# ESC-1.net
KiCad netlist of a schematic drawn in EAGLE
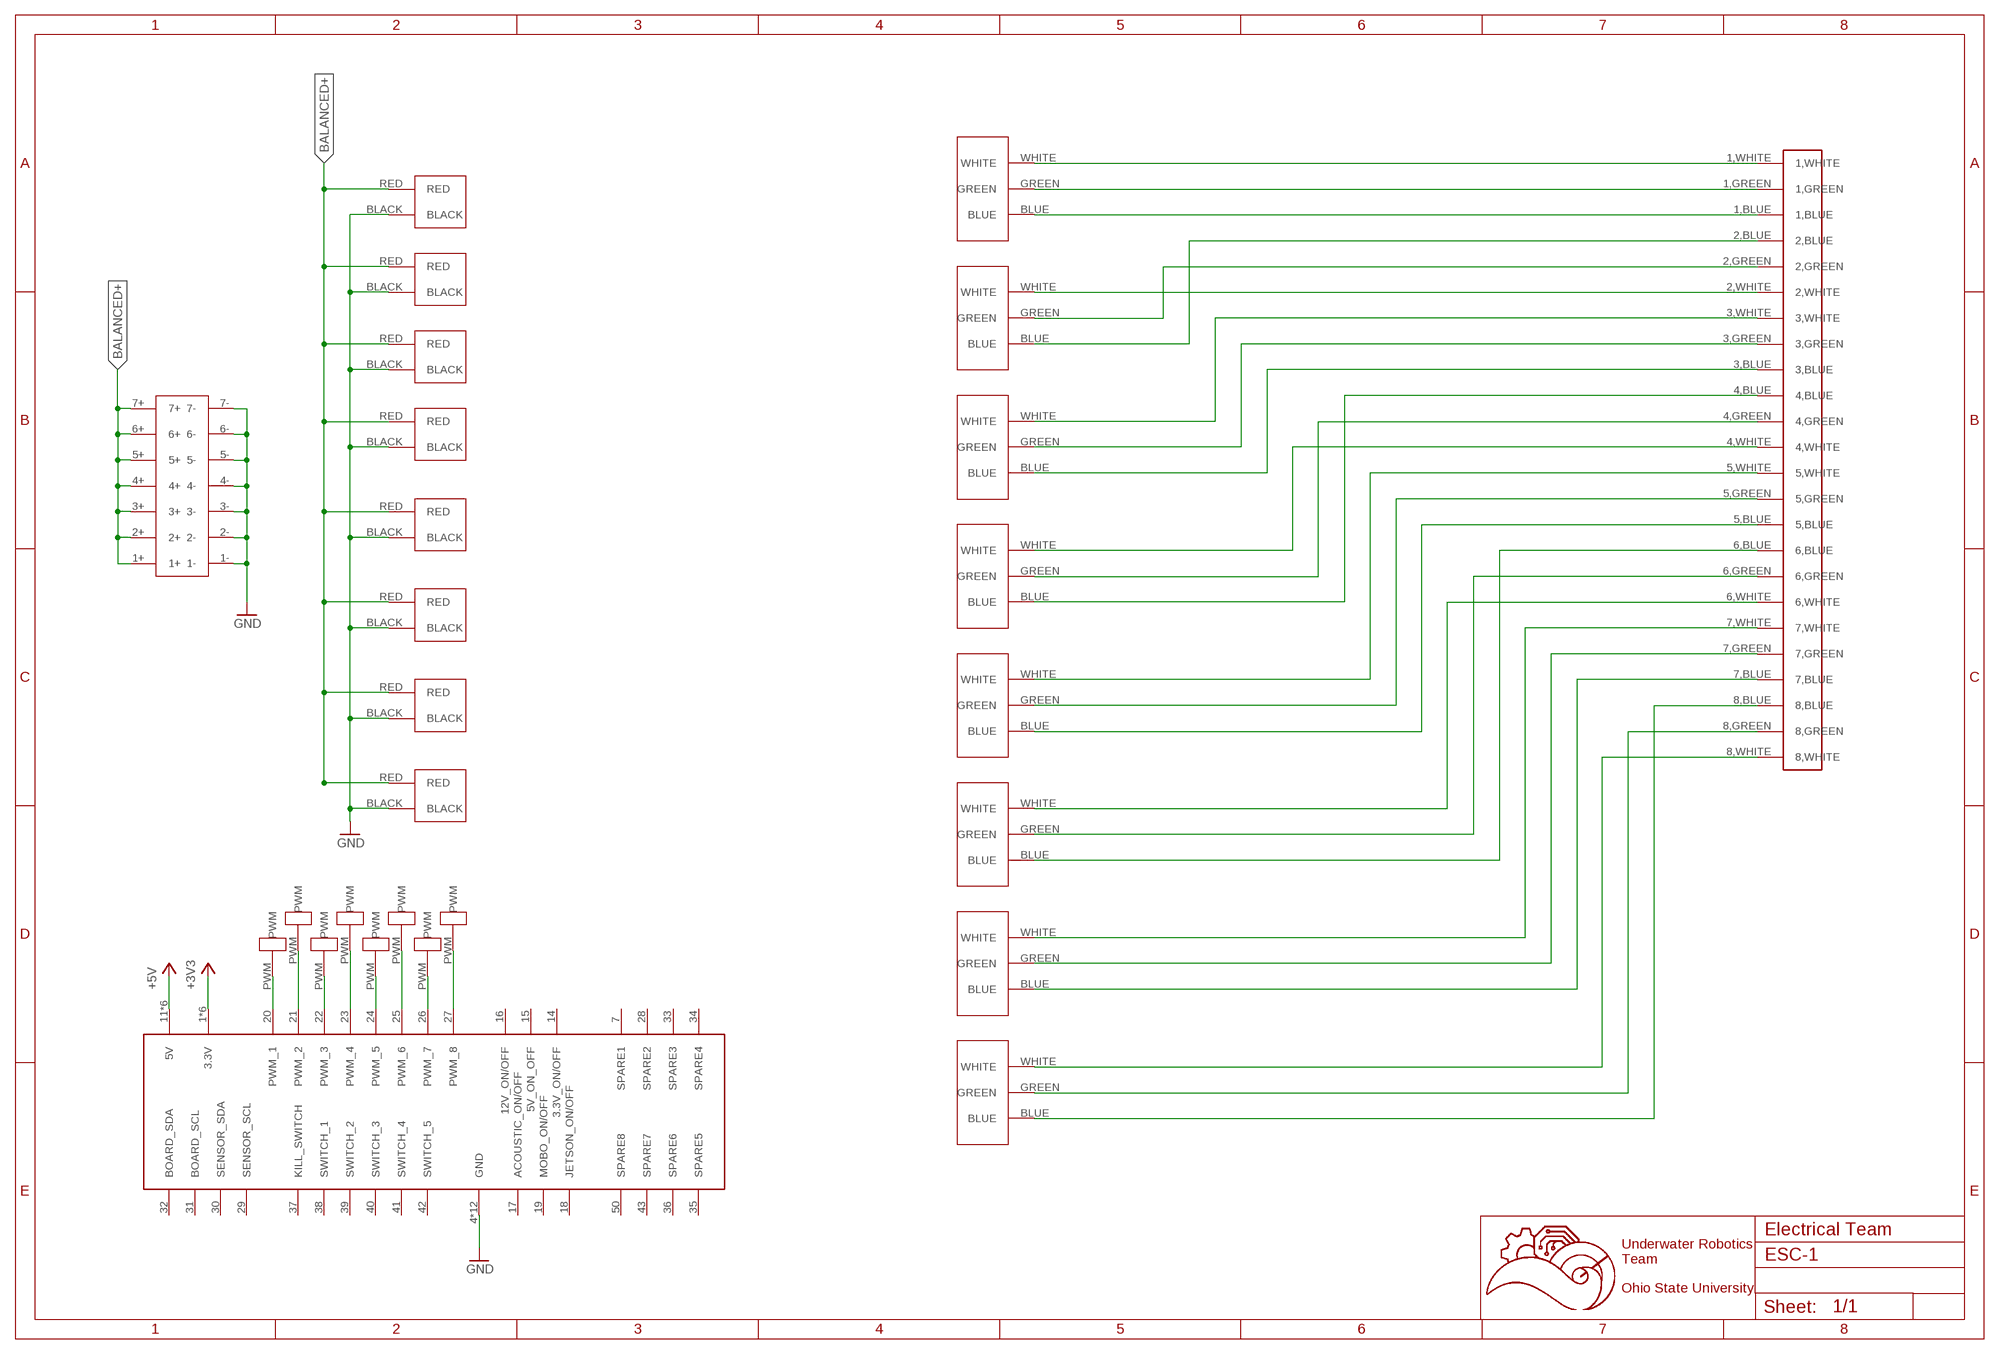
[diagram p0: schematic, sheet 1]

(export (version "E")
  (design (tool "Eeschema 10.0.6"))
  (components
    (comp (ref "1")
      (value "1711738")
      (footprint "eagle-import:1711738")
      (libsource (lib "eagle-import") (part "1711738"))
    )
    (comp (ref "2")
      (value "1711738")
      (footprint "eagle-import:1711738")
      (libsource (lib "eagle-import") (part "1711738"))
    )
    (comp (ref "3")
      (value "1711738")
      (footprint "eagle-import:1711738")
      (libsource (lib "eagle-import") (part "1711738"))
    )
    (comp (ref "4")
      (value "1711738")
      (footprint "eagle-import:1711738")
      (libsource (lib "eagle-import") (part "1711738"))
    )
    (comp (ref "5")
      (value "1711738")
      (footprint "eagle-import:1711738")
      (libsource (lib "eagle-import") (part "1711738"))
    )
    (comp (ref "6")
      (value "1711738")
      (footprint "eagle-import:1711738")
      (libsource (lib "eagle-import") (part "1711738"))
    )
    (comp (ref "7")
      (value "1711738")
      (footprint "eagle-import:1711738")
      (libsource (lib "eagle-import") (part "1711738"))
    )
    (comp (ref "8")
      (value "1711738")
      (footprint "eagle-import:1711738")
      (libsource (lib "eagle-import") (part "1711738"))
    )
    (comp (ref "U$1")
      (value "5530843-EDGE")
      (footprint "eagle-import:5530843-6-BOARDFINGERS")
      (libsource (lib "eagle-import") (part "5530843-EDGE"))
    )
    (comp (ref "U$2")
      (value "1711725")
      (footprint "eagle-import:1711725")
      (libsource (lib "eagle-import") (part "1711725"))
    )
    (comp (ref "U$3")
      (value "1711725")
      (footprint "eagle-import:1711725")
      (libsource (lib "eagle-import") (part "1711725"))
    )
    (comp (ref "U$4")
      (value "1711725")
      (footprint "eagle-import:1711725")
      (libsource (lib "eagle-import") (part "1711725"))
    )
    (comp (ref "U$5")
      (value "1711725")
      (footprint "eagle-import:1711725")
      (libsource (lib "eagle-import") (part "1711725"))
    )
    (comp (ref "U$6")
      (value "1711725")
      (footprint "eagle-import:1711725")
      (libsource (lib "eagle-import") (part "1711725"))
    )
    (comp (ref "U$7")
      (value "1711725")
      (footprint "eagle-import:1711725")
      (libsource (lib "eagle-import") (part "1711725"))
    )
    (comp (ref "U$8")
      (value "1711725")
      (footprint "eagle-import:1711725")
      (libsource (lib "eagle-import") (part "1711725"))
    )
    (comp (ref "U$9")
      (value "1711725")
      (footprint "eagle-import:1711725")
      (libsource (lib "eagle-import") (part "1711725"))
    )
    (comp (ref "U$18")
      (value "24PINCONVERTER")
      (footprint "eagle-import:24PINCONVERTER")
      (libsource (lib "eagle-import") (part "24PINCONVERTER"))
    )
    (comp (ref "U$19")
      (value "14PIN_VERT")
      (footprint "eagle-import:14PIN_VERT")
      (libsource (lib "eagle-import") (part "14PIN_VERT"))
    )
    (comp (ref "U$20")
      (value "MALE1PINHEADER")
      (footprint "eagle-import:MALE1PINHEADER")
      (libsource (lib "eagle-import") (part "MALE1PINHEADER"))
    )
    (comp (ref "U$21")
      (value "MALE1PINHEADER")
      (footprint "eagle-import:MALE1PINHEADER")
      (libsource (lib "eagle-import") (part "MALE1PINHEADER"))
    )
    (comp (ref "U$22")
      (value "MALE1PINHEADER")
      (footprint "eagle-import:MALE1PINHEADER")
      (libsource (lib "eagle-import") (part "MALE1PINHEADER"))
    )
    (comp (ref "U$23")
      (value "MALE1PINHEADER")
      (footprint "eagle-import:MALE1PINHEADER")
      (libsource (lib "eagle-import") (part "MALE1PINHEADER"))
    )
    (comp (ref "U$24")
      (value "MALE1PINHEADER")
      (footprint "eagle-import:MALE1PINHEADER")
      (libsource (lib "eagle-import") (part "MALE1PINHEADER"))
    )
    (comp (ref "U$25")
      (value "MALE1PINHEADER")
      (footprint "eagle-import:MALE1PINHEADER")
      (libsource (lib "eagle-import") (part "MALE1PINHEADER"))
    )
    (comp (ref "U$26")
      (value "MALE1PINHEADER")
      (footprint "eagle-import:MALE1PINHEADER")
      (libsource (lib "eagle-import") (part "MALE1PINHEADER"))
    )
    (comp (ref "U$27")
      (value "MALE1PINHEADER")
      (footprint "eagle-import:MALE1PINHEADER")
      (libsource (lib "eagle-import") (part "MALE1PINHEADER"))
    )
  )
  (nets
    (net (code "1") (name "+3V3") (class "Default")
      (node (ref "U$1") (pin "1") (pinfunction "3.3V_1") (pintype "bidirectional"))
      (node (ref "U$1") (pin "2") (pinfunction "3.3V_2") (pintype "bidirectional"))
      (node (ref "U$1") (pin "3") (pinfunction "3.3V_3") (pintype "bidirectional"))
      (node (ref "U$1") (pin "54") (pinfunction "3.3V_54") (pintype "bidirectional"))
      (node (ref "U$1") (pin "55") (pinfunction "3.3V_55") (pintype "bidirectional"))
      (node (ref "U$1") (pin "56") (pinfunction "3.3V_56") (pintype "bidirectional"))
    )
    (net (code "2") (name "+5V") (class "Default")
      (node (ref "U$1") (pin "11") (pinfunction "5V_11") (pintype "bidirectional"))
      (node (ref "U$1") (pin "12") (pinfunction "5V_12") (pintype "bidirectional"))
      (node (ref "U$1") (pin "13") (pinfunction "5V_13") (pintype "bidirectional"))
      (node (ref "U$1") (pin "44") (pinfunction "5V_44") (pintype "bidirectional"))
      (node (ref "U$1") (pin "45") (pinfunction "5V_45") (pintype "bidirectional"))
      (node (ref "U$1") (pin "46") (pinfunction "5V_46") (pintype "bidirectional"))
    )
    (net (code "3") (name "BALANCED+") (class "Default")
      (node (ref "U$19") (pin "1+") (pinfunction "1+_1+") (pintype "bidirectional"))
      (node (ref "U$19") (pin "2+") (pinfunction "2+_2+") (pintype "bidirectional"))
      (node (ref "U$19") (pin "3+") (pinfunction "3+_3+") (pintype "bidirectional"))
      (node (ref "U$19") (pin "4+") (pinfunction "4+_4+") (pintype "bidirectional"))
      (node (ref "U$19") (pin "5+") (pinfunction "5+_5+") (pintype "bidirectional"))
      (node (ref "U$19") (pin "6+") (pinfunction "6+_6+") (pintype "bidirectional"))
      (node (ref "U$19") (pin "7+") (pinfunction "7+_7+") (pintype "bidirectional"))
      (node (ref "U$2") (pin "RED") (pinfunction "RED_RED") (pintype "bidirectional"))
      (node (ref "U$3") (pin "RED") (pinfunction "RED_RED") (pintype "bidirectional"))
      (node (ref "U$4") (pin "RED") (pinfunction "RED_RED") (pintype "bidirectional"))
      (node (ref "U$5") (pin "RED") (pinfunction "RED_RED") (pintype "bidirectional"))
      (node (ref "U$6") (pin "RED") (pinfunction "RED_RED") (pintype "bidirectional"))
      (node (ref "U$7") (pin "RED") (pinfunction "RED_RED") (pintype "bidirectional"))
      (node (ref "U$8") (pin "RED") (pinfunction "RED_RED") (pintype "bidirectional"))
      (node (ref "U$9") (pin "RED") (pinfunction "RED_RED") (pintype "bidirectional"))
    )
    (net (code "4") (name "GND") (class "Default")
      (node (ref "U$1") (pin "10") (pinfunction "GND_10") (pintype "bidirectional"))
      (node (ref "U$1") (pin "4") (pinfunction "GND_4") (pintype "bidirectional"))
      (node (ref "U$1") (pin "47") (pinfunction "GND_47") (pintype "bidirectional"))
      (node (ref "U$1") (pin "48") (pinfunction "GND_48") (pintype "bidirectional"))
      (node (ref "U$1") (pin "49") (pinfunction "GND_49") (pintype "bidirectional"))
      (node (ref "U$1") (pin "5") (pinfunction "GND_5") (pintype "bidirectional"))
      (node (ref "U$1") (pin "51") (pinfunction "GND_51") (pintype "bidirectional"))
      (node (ref "U$1") (pin "52") (pinfunction "GND_52") (pintype "bidirectional"))
      (node (ref "U$1") (pin "53") (pinfunction "GND_53") (pintype "bidirectional"))
      (node (ref "U$1") (pin "6") (pinfunction "GND_6") (pintype "bidirectional"))
      (node (ref "U$1") (pin "8") (pinfunction "GND_8") (pintype "bidirectional"))
      (node (ref "U$1") (pin "9") (pinfunction "GND_9") (pintype "bidirectional"))
      (node (ref "U$19") (pin "1-") (pinfunction "1-_1-") (pintype "bidirectional"))
      (node (ref "U$19") (pin "2-") (pinfunction "2-_2-") (pintype "bidirectional"))
      (node (ref "U$19") (pin "3-") (pinfunction "3-_3-") (pintype "bidirectional"))
      (node (ref "U$19") (pin "4-") (pinfunction "4-_4-") (pintype "bidirectional"))
      (node (ref "U$19") (pin "5-") (pinfunction "5-_5-") (pintype "bidirectional"))
      (node (ref "U$19") (pin "6-") (pinfunction "6-_6-") (pintype "bidirectional"))
      (node (ref "U$19") (pin "7-") (pinfunction "7-_7-") (pintype "bidirectional"))
      (node (ref "U$2") (pin "BLACK") (pinfunction "BLACK_BLACK") (pintype "bidirectional"))
      (node (ref "U$3") (pin "BLACK") (pinfunction "BLACK_BLACK") (pintype "bidirectional"))
      (node (ref "U$4") (pin "BLACK") (pinfunction "BLACK_BLACK") (pintype "bidirectional"))
      (node (ref "U$5") (pin "BLACK") (pinfunction "BLACK_BLACK") (pintype "bidirectional"))
      (node (ref "U$6") (pin "BLACK") (pinfunction "BLACK_BLACK") (pintype "bidirectional"))
      (node (ref "U$7") (pin "BLACK") (pinfunction "BLACK_BLACK") (pintype "bidirectional"))
      (node (ref "U$8") (pin "BLACK") (pinfunction "BLACK_BLACK") (pintype "bidirectional"))
      (node (ref "U$9") (pin "BLACK") (pinfunction "BLACK_BLACK") (pintype "bidirectional"))
    )
    (net (code "5") (name "Net-(1-PadBLUE)") (class "Default")
      (node (ref "1") (pin "BLUE") (pinfunction "BLUE_BLUE") (pintype "bidirectional"))
      (node (ref "U$18") (pin "1,BLUE") (pinfunction "1,BLUE_1,BLUE") (pintype "bidirectional"))
    )
    (net (code "6") (name "Net-(1-PadGREEN)") (class "Default")
      (node (ref "1") (pin "GREEN") (pinfunction "GREEN_GREEN") (pintype "bidirectional"))
      (node (ref "U$18") (pin "1,GREEN") (pinfunction "1,GREEN_1,GREEN") (pintype "bidirectional"))
    )
    (net (code "7") (name "Net-(1-PadWHITE)") (class "Default")
      (node (ref "1") (pin "WHITE") (pinfunction "WHITE_WHITE") (pintype "bidirectional"))
      (node (ref "U$18") (pin "1,WHITE") (pinfunction "1,WHITE_1,WHITE") (pintype "bidirectional"))
    )
    (net (code "8") (name "Net-(2-PadBLUE)") (class "Default")
      (node (ref "2") (pin "BLUE") (pinfunction "BLUE_BLUE") (pintype "bidirectional"))
      (node (ref "U$18") (pin "2,BLUE") (pinfunction "2,BLUE_2,BLUE") (pintype "bidirectional"))
    )
    (net (code "9") (name "Net-(2-PadGREEN)") (class "Default")
      (node (ref "2") (pin "GREEN") (pinfunction "GREEN_GREEN") (pintype "bidirectional"))
      (node (ref "U$18") (pin "2,GREEN") (pinfunction "2,GREEN_2,GREEN") (pintype "bidirectional"))
    )
    (net (code "10") (name "Net-(2-PadWHITE)") (class "Default")
      (node (ref "2") (pin "WHITE") (pinfunction "WHITE_WHITE") (pintype "bidirectional"))
      (node (ref "U$18") (pin "2,WHITE") (pinfunction "2,WHITE_2,WHITE") (pintype "bidirectional"))
    )
    (net (code "11") (name "Net-(3-PadBLUE)") (class "Default")
      (node (ref "3") (pin "BLUE") (pinfunction "BLUE_BLUE") (pintype "bidirectional"))
      (node (ref "U$18") (pin "3,BLUE") (pinfunction "3,BLUE_3,BLUE") (pintype "bidirectional"))
    )
    (net (code "12") (name "Net-(3-PadGREEN)") (class "Default")
      (node (ref "3") (pin "GREEN") (pinfunction "GREEN_GREEN") (pintype "bidirectional"))
      (node (ref "U$18") (pin "3,GREEN") (pinfunction "3,GREEN_3,GREEN") (pintype "bidirectional"))
    )
    (net (code "13") (name "Net-(3-PadWHITE)") (class "Default")
      (node (ref "3") (pin "WHITE") (pinfunction "WHITE_WHITE") (pintype "bidirectional"))
      (node (ref "U$18") (pin "3,WHITE") (pinfunction "3,WHITE_3,WHITE") (pintype "bidirectional"))
    )
    (net (code "14") (name "Net-(4-PadBLUE)") (class "Default")
      (node (ref "4") (pin "BLUE") (pinfunction "BLUE_BLUE") (pintype "bidirectional"))
      (node (ref "U$18") (pin "4,BLUE") (pinfunction "4,BLUE_4,BLUE") (pintype "bidirectional"))
    )
    (net (code "15") (name "Net-(4-PadGREEN)") (class "Default")
      (node (ref "4") (pin "GREEN") (pinfunction "GREEN_GREEN") (pintype "bidirectional"))
      (node (ref "U$18") (pin "4,GREEN") (pinfunction "4,GREEN_4,GREEN") (pintype "bidirectional"))
    )
    (net (code "16") (name "Net-(4-PadWHITE)") (class "Default")
      (node (ref "4") (pin "WHITE") (pinfunction "WHITE_WHITE") (pintype "bidirectional"))
      (node (ref "U$18") (pin "4,WHITE") (pinfunction "4,WHITE_4,WHITE") (pintype "bidirectional"))
    )
    (net (code "17") (name "Net-(5-PadBLUE)") (class "Default")
      (node (ref "5") (pin "BLUE") (pinfunction "BLUE_BLUE") (pintype "bidirectional"))
      (node (ref "U$18") (pin "5,BLUE") (pinfunction "5,BLUE_5,BLUE") (pintype "bidirectional"))
    )
    (net (code "18") (name "Net-(5-PadGREEN)") (class "Default")
      (node (ref "5") (pin "GREEN") (pinfunction "GREEN_GREEN") (pintype "bidirectional"))
      (node (ref "U$18") (pin "5,GREEN") (pinfunction "5,GREEN_5,GREEN") (pintype "bidirectional"))
    )
    (net (code "19") (name "Net-(5-PadWHITE)") (class "Default")
      (node (ref "5") (pin "WHITE") (pinfunction "WHITE_WHITE") (pintype "bidirectional"))
      (node (ref "U$18") (pin "5,WHITE") (pinfunction "5,WHITE_5,WHITE") (pintype "bidirectional"))
    )
    (net (code "20") (name "Net-(6-PadBLUE)") (class "Default")
      (node (ref "6") (pin "BLUE") (pinfunction "BLUE_BLUE") (pintype "bidirectional"))
      (node (ref "U$18") (pin "6,BLUE") (pinfunction "6,BLUE_6,BLUE") (pintype "bidirectional"))
    )
    (net (code "21") (name "Net-(6-PadGREEN)") (class "Default")
      (node (ref "6") (pin "GREEN") (pinfunction "GREEN_GREEN") (pintype "bidirectional"))
      (node (ref "U$18") (pin "6,GREEN") (pinfunction "6,GREEN_6,GREEN") (pintype "bidirectional"))
    )
    (net (code "22") (name "Net-(6-PadWHITE)") (class "Default")
      (node (ref "6") (pin "WHITE") (pinfunction "WHITE_WHITE") (pintype "bidirectional"))
      (node (ref "U$18") (pin "6,WHITE") (pinfunction "6,WHITE_6,WHITE") (pintype "bidirectional"))
    )
    (net (code "23") (name "Net-(7-PadBLUE)") (class "Default")
      (node (ref "7") (pin "BLUE") (pinfunction "BLUE_BLUE") (pintype "bidirectional"))
      (node (ref "U$18") (pin "7,BLUE") (pinfunction "7,BLUE_7,BLUE") (pintype "bidirectional"))
    )
    (net (code "24") (name "Net-(7-PadGREEN)") (class "Default")
      (node (ref "7") (pin "GREEN") (pinfunction "GREEN_GREEN") (pintype "bidirectional"))
      (node (ref "U$18") (pin "7,GREEN") (pinfunction "7,GREEN_7,GREEN") (pintype "bidirectional"))
    )
    (net (code "25") (name "Net-(7-PadWHITE)") (class "Default")
      (node (ref "7") (pin "WHITE") (pinfunction "WHITE_WHITE") (pintype "bidirectional"))
      (node (ref "U$18") (pin "7,WHITE") (pinfunction "7,WHITE_7,WHITE") (pintype "bidirectional"))
    )
    (net (code "26") (name "Net-(8-PadBLUE)") (class "Default")
      (node (ref "8") (pin "BLUE") (pinfunction "BLUE_BLUE") (pintype "bidirectional"))
      (node (ref "U$18") (pin "8,BLUE") (pinfunction "8,BLUE_8,BLUE") (pintype "bidirectional"))
    )
    (net (code "27") (name "Net-(8-PadGREEN)") (class "Default")
      (node (ref "8") (pin "GREEN") (pinfunction "GREEN_GREEN") (pintype "bidirectional"))
      (node (ref "U$18") (pin "8,GREEN") (pinfunction "8,GREEN_8,GREEN") (pintype "bidirectional"))
    )
    (net (code "28") (name "Net-(8-PadWHITE)") (class "Default")
      (node (ref "8") (pin "WHITE") (pinfunction "WHITE_WHITE") (pintype "bidirectional"))
      (node (ref "U$18") (pin "8,WHITE") (pinfunction "8,WHITE_8,WHITE") (pintype "bidirectional"))
    )
    (net (code "29") (name "Net-(U$1-PWM_1)") (class "Default")
      (node (ref "U$1") (pin "20") (pinfunction "PWM_1_20") (pintype "bidirectional"))
      (node (ref "U$20") (pin "PWM") (pinfunction "PWM_PWM") (pintype "bidirectional"))
    )
    (net (code "30") (name "Net-(U$1-PWM_2)") (class "Default")
      (node (ref "U$1") (pin "21") (pinfunction "PWM_2_21") (pintype "bidirectional"))
      (node (ref "U$21") (pin "PWM") (pinfunction "PWM_PWM") (pintype "bidirectional"))
    )
    (net (code "31") (name "Net-(U$1-PWM_3)") (class "Default")
      (node (ref "U$1") (pin "22") (pinfunction "PWM_3_22") (pintype "bidirectional"))
      (node (ref "U$22") (pin "PWM") (pinfunction "PWM_PWM") (pintype "bidirectional"))
    )
    (net (code "32") (name "Net-(U$1-PWM_4)") (class "Default")
      (node (ref "U$1") (pin "23") (pinfunction "PWM_4_23") (pintype "bidirectional"))
      (node (ref "U$23") (pin "PWM") (pinfunction "PWM_PWM") (pintype "bidirectional"))
    )
    (net (code "33") (name "Net-(U$1-PWM_5)") (class "Default")
      (node (ref "U$1") (pin "24") (pinfunction "PWM_5_24") (pintype "bidirectional"))
      (node (ref "U$24") (pin "PWM") (pinfunction "PWM_PWM") (pintype "bidirectional"))
    )
    (net (code "34") (name "Net-(U$1-PWM_6)") (class "Default")
      (node (ref "U$1") (pin "25") (pinfunction "PWM_6_25") (pintype "bidirectional"))
      (node (ref "U$25") (pin "PWM") (pinfunction "PWM_PWM") (pintype "bidirectional"))
    )
    (net (code "35") (name "Net-(U$1-PWM_7)") (class "Default")
      (node (ref "U$1") (pin "26") (pinfunction "PWM_7_26") (pintype "bidirectional"))
      (node (ref "U$26") (pin "PWM") (pinfunction "PWM_PWM") (pintype "bidirectional"))
    )
    (net (code "36") (name "Net-(U$1-PWM_8)") (class "Default")
      (node (ref "U$1") (pin "27") (pinfunction "PWM_8_27") (pintype "bidirectional"))
      (node (ref "U$27") (pin "PWM") (pinfunction "PWM_PWM") (pintype "bidirectional"))
    )
    (net (code "37") (name "unconnected-(U$1-3.3V_ON{slash}OFF-Pad14)") (class "Default")
      (node (ref "U$1") (pin "14") (pinfunction "3.3V_ON/OFF_14") (pintype "bidirectional"))
    )
    (net (code "38") (name "unconnected-(U$1-5V_ON_OFF-Pad15)") (class "Default")
      (node (ref "U$1") (pin "15") (pinfunction "5V_ON_OFF_15") (pintype "bidirectional"))
    )
    (net (code "39") (name "unconnected-(U$1-12V_ON{slash}OFF-Pad16)") (class "Default")
      (node (ref "U$1") (pin "16") (pinfunction "12V_ON/OFF_16") (pintype "bidirectional"))
    )
    (net (code "40") (name "unconnected-(U$1-ACOUSTIC_ON{slash}OFF-Pad17)") (class "Default")
      (node (ref "U$1") (pin "17") (pinfunction "ACOUSTIC_ON/OFF_17") (pintype "bidirectional"))
    )
    (net (code "41") (name "unconnected-(U$1-BOARD_SCL-Pad31)") (class "Default")
      (node (ref "U$1") (pin "31") (pinfunction "BOARD_SCL_31") (pintype "bidirectional"))
    )
    (net (code "42") (name "unconnected-(U$1-BOARD_SDA-Pad32)") (class "Default")
      (node (ref "U$1") (pin "32") (pinfunction "BOARD_SDA_32") (pintype "bidirectional"))
    )
    (net (code "43") (name "unconnected-(U$1-JETSON_ON{slash}OFF-Pad18)") (class "Default")
      (node (ref "U$1") (pin "18") (pinfunction "JETSON_ON/OFF_18") (pintype "bidirectional"))
    )
    (net (code "44") (name "unconnected-(U$1-KILL_SWITCH-Pad37)") (class "Default")
      (node (ref "U$1") (pin "37") (pinfunction "KILL_SWITCH_37") (pintype "output"))
    )
    (net (code "45") (name "unconnected-(U$1-MOBO_ON{slash}OFF-Pad19)") (class "Default")
      (node (ref "U$1") (pin "19") (pinfunction "MOBO_ON/OFF_19") (pintype "bidirectional"))
    )
    (net (code "46") (name "unconnected-(U$1-SENSOR_SCL-Pad29)") (class "Default")
      (node (ref "U$1") (pin "29") (pinfunction "SENSOR_SCL_29") (pintype "bidirectional"))
    )
    (net (code "47") (name "unconnected-(U$1-SENSOR_SDA-Pad30)") (class "Default")
      (node (ref "U$1") (pin "30") (pinfunction "SENSOR_SDA_30") (pintype "bidirectional"))
    )
    (net (code "48") (name "unconnected-(U$1-SPARE1-Pad7)") (class "Default")
      (node (ref "U$1") (pin "7") (pinfunction "SPARE1_7") (pintype "bidirectional"))
    )
    (net (code "49") (name "unconnected-(U$1-SPARE2-Pad28)") (class "Default")
      (node (ref "U$1") (pin "28") (pinfunction "SPARE2_28") (pintype "bidirectional"))
    )
    (net (code "50") (name "unconnected-(U$1-SPARE3-Pad33)") (class "Default")
      (node (ref "U$1") (pin "33") (pinfunction "SPARE3_33") (pintype "bidirectional"))
    )
    (net (code "51") (name "unconnected-(U$1-SPARE4-Pad34)") (class "Default")
      (node (ref "U$1") (pin "34") (pinfunction "SPARE4_34") (pintype "bidirectional"))
    )
    (net (code "52") (name "unconnected-(U$1-SPARE5-Pad35)") (class "Default")
      (node (ref "U$1") (pin "35") (pinfunction "SPARE5_35") (pintype "bidirectional"))
    )
    (net (code "53") (name "unconnected-(U$1-SPARE6-Pad36)") (class "Default")
      (node (ref "U$1") (pin "36") (pinfunction "SPARE6_36") (pintype "bidirectional"))
    )
    (net (code "54") (name "unconnected-(U$1-SPARE7-Pad43)") (class "Default")
      (node (ref "U$1") (pin "43") (pinfunction "SPARE7_43") (pintype "bidirectional"))
    )
    (net (code "55") (name "unconnected-(U$1-SPARE8-Pad50)") (class "Default")
      (node (ref "U$1") (pin "50") (pinfunction "SPARE8_50") (pintype "bidirectional"))
    )
    (net (code "56") (name "unconnected-(U$1-SWITCH_1-Pad38)") (class "Default")
      (node (ref "U$1") (pin "38") (pinfunction "SWITCH_1_38") (pintype "output"))
    )
    (net (code "57") (name "unconnected-(U$1-SWITCH_2-Pad39)") (class "Default")
      (node (ref "U$1") (pin "39") (pinfunction "SWITCH_2_39") (pintype "output"))
    )
    (net (code "58") (name "unconnected-(U$1-SWITCH_3-Pad40)") (class "Default")
      (node (ref "U$1") (pin "40") (pinfunction "SWITCH_3_40") (pintype "output"))
    )
    (net (code "59") (name "unconnected-(U$1-SWITCH_4-Pad41)") (class "Default")
      (node (ref "U$1") (pin "41") (pinfunction "SWITCH_4_41") (pintype "output"))
    )
    (net (code "60") (name "unconnected-(U$1-SWITCH_5-Pad42)") (class "Default")
      (node (ref "U$1") (pin "42") (pinfunction "SWITCH_5_42") (pintype "output"))
    )
  )
)
